# Controller.net
KiCad netlist of a schematic drawn in Altium Designer
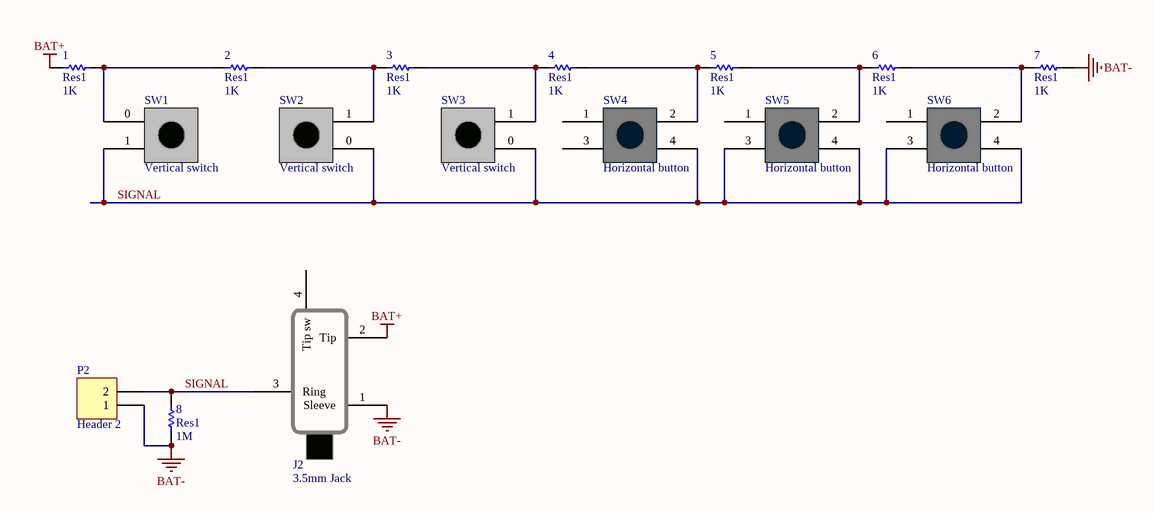
[diagram p0: Controller.SchDoc]

(export (version "E")
  (design (tool "Eeschema 10.0.6"))
  (components
    (comp (ref "1")
      (value "Res1")
      (footprint "6-0805_N")
      (description "Resistor")
      (fields (field (name "ALTIUM_VALUE") "1K") (field (name "PUBLISHER") "Altium Limited"))
      (libsource (lib "Miscellaneous Devices") (part "Res1"))
    )
    (comp (ref "2")
      (value "Res1")
      (footprint "6-0805_N")
      (description "Resistor")
      (fields (field (name "ALTIUM_VALUE") "1K") (field (name "PUBLISHER") "Altium Limited"))
      (libsource (lib "Miscellaneous Devices") (part "Res1"))
    )
    (comp (ref "3")
      (value "Res1")
      (footprint "6-0805_N")
      (description "Resistor")
      (fields (field (name "ALTIUM_VALUE") "1K") (field (name "PUBLISHER") "Altium Limited"))
      (libsource (lib "Miscellaneous Devices") (part "Res1"))
    )
    (comp (ref "4")
      (value "Res1")
      (footprint "6-0805_N")
      (description "Resistor")
      (fields (field (name "ALTIUM_VALUE") "1K") (field (name "PUBLISHER") "Altium Limited"))
      (libsource (lib "Miscellaneous Devices") (part "Res1"))
    )
    (comp (ref "5")
      (value "Res1")
      (footprint "6-0805_N")
      (description "Resistor")
      (fields (field (name "ALTIUM_VALUE") "1K") (field (name "PUBLISHER") "Altium Limited"))
      (libsource (lib "Miscellaneous Devices") (part "Res1"))
    )
    (comp (ref "6")
      (value "Res1")
      (footprint "6-0805_N")
      (description "Resistor")
      (fields (field (name "ALTIUM_VALUE") "1K") (field (name "PUBLISHER") "Altium Limited"))
      (libsource (lib "Miscellaneous Devices") (part "Res1"))
    )
    (comp (ref "7")
      (value "Res1")
      (footprint "6-0805_N")
      (description "Resistor")
      (fields (field (name "ALTIUM_VALUE") "1K") (field (name "PUBLISHER") "Altium Limited"))
      (libsource (lib "Miscellaneous Devices") (part "Res1"))
    )
    (comp (ref "8")
      (value "Res1")
      (footprint "6-0805_M")
      (description "Resistor")
      (fields (field (name "ALTIUM_VALUE") "1M") (field (name "PUBLISHER") "Altium Limited"))
      (libsource (lib "Miscellaneous Devices") (part "Res1"))
    )
    (comp (ref "J2")
      (value "3.5mm Jack")
      (footprint "Phonejack")
      (libsource (lib "Phonejack") (part "Phonejack"))
    )
    (comp (ref "P2")
      (value "Header 2")
      (footprint "HDR1X2")
      (description "Header, 2-Pin")
      (fields (field (name "PUBLISHER") "Altium Limited"))
      (libsource (lib "Miscellaneous Connectors") (part "Header 2"))
    )
    (comp (ref "SW1") (value "Vertical switch") (footprint "Btn_Vert") (libsource (lib "") (part "SWVERT_1")))
    (comp (ref "SW2")
      (value "Vertical switch")
      (footprint "Btn_Vert")
      (libsource (lib "Btn_Vert") (part "SWVERT"))
    )
    (comp (ref "SW3")
      (value "Vertical switch")
      (footprint "Btn_Vert")
      (libsource (lib "Btn_Vert") (part "SWVERT"))
    )
    (comp (ref "SW4")
      (value "Horizontal button")
      (footprint "Btn_Horiz")
      (libsource (lib "Btn_Horiz") (part "HORIZBTN"))
    )
    (comp (ref "SW5")
      (value "Horizontal button")
      (footprint "Btn_Horiz")
      (libsource (lib "Btn_Horiz") (part "HORIZBTN"))
    )
    (comp (ref "SW6")
      (value "Horizontal button")
      (footprint "Btn_Horiz")
      (libsource (lib "Btn_Horiz") (part "HORIZBTN"))
    )
  )
  (nets
    (net (code "1") (name "/SIGNAL") (class "Default")
      (node (ref "8") (pin "1") (pinfunction "1_1") (pintype "passive"))
      (node (ref "J2") (pin "3") (pinfunction "Ring_3") (pintype "passive"))
      (node (ref "P2") (pin "2") (pinfunction "2_2") (pintype "passive"))
      (node (ref "SW1") (pin "1") (pintype "passive"))
      (node (ref "SW2") (pin "0") (pintype "passive"))
      (node (ref "SW3") (pin "0") (pintype "passive"))
      (node (ref "SW4") (pin "4") (pintype "passive"))
      (node (ref "SW5") (pin "3") (pintype "passive"))
      (node (ref "SW5") (pin "4") (pintype "passive"))
      (node (ref "SW6") (pin "3") (pintype "passive"))
      (node (ref "SW6") (pin "4") (pintype "passive"))
    )
    (net (code "2") (name "BAT+") (class "Default")
      (node (ref "1") (pin "2") (pinfunction "2_2") (pintype "passive"))
      (node (ref "J2") (pin "2") (pinfunction "Tip_2") (pintype "passive"))
    )
    (net (code "3") (name "BAT-") (class "Default")
      (node (ref "7") (pin "1") (pinfunction "1_1") (pintype "passive"))
      (node (ref "8") (pin "2") (pinfunction "2_2") (pintype "passive"))
      (node (ref "J2") (pin "1") (pinfunction "Sleeve_1") (pintype "passive"))
      (node (ref "P2") (pin "1") (pinfunction "1_1") (pintype "passive"))
    )
    (net (code "4") (name "Net-(1-Pad1)") (class "Default")
      (node (ref "1") (pin "1") (pinfunction "1_1") (pintype "passive"))
      (node (ref "2") (pin "2") (pinfunction "2_2") (pintype "passive"))
      (node (ref "SW1") (pin "0") (pintype "passive"))
    )
    (net (code "5") (name "Net-(2-Pad1)") (class "Default")
      (node (ref "2") (pin "1") (pinfunction "1_1") (pintype "passive"))
      (node (ref "3") (pin "2") (pinfunction "2_2") (pintype "passive"))
      (node (ref "SW2") (pin "1") (pintype "passive"))
    )
    (net (code "6") (name "Net-(3-Pad1)") (class "Default")
      (node (ref "3") (pin "1") (pinfunction "1_1") (pintype "passive"))
      (node (ref "4") (pin "2") (pinfunction "2_2") (pintype "passive"))
      (node (ref "SW3") (pin "1") (pintype "passive"))
    )
    (net (code "7") (name "Net-(4-Pad1)") (class "Default")
      (node (ref "4") (pin "1") (pinfunction "1_1") (pintype "passive"))
      (node (ref "5") (pin "2") (pinfunction "2_2") (pintype "passive"))
      (node (ref "SW4") (pin "2") (pintype "passive"))
    )
    (net (code "8") (name "Net-(5-Pad1)") (class "Default")
      (node (ref "5") (pin "1") (pinfunction "1_1") (pintype "passive"))
      (node (ref "6") (pin "1") (pinfunction "1_1") (pintype "passive"))
      (node (ref "SW5") (pin "2") (pintype "passive"))
    )
    (net (code "9") (name "Net-(6-Pad2)") (class "Default")
      (node (ref "6") (pin "2") (pinfunction "2_2") (pintype "passive"))
      (node (ref "7") (pin "2") (pinfunction "2_2") (pintype "passive"))
      (node (ref "SW6") (pin "2") (pintype "passive"))
    )
    (net (code "10") (name "unconnected-(J2-Tip_sw-Pad4)") (class "Default")
      (node (ref "J2") (pin "4") (pinfunction "Tip_sw_4") (pintype "passive"))
    )
    (net (code "11") (name "unconnected-(SW4-Pad1)") (class "Default")
      (node (ref "SW4") (pin "1") (pintype "passive"))
    )
    (net (code "12") (name "unconnected-(SW4-Pad3)") (class "Default")
      (node (ref "SW4") (pin "3") (pintype "passive"))
    )
    (net (code "13") (name "unconnected-(SW5-Pad1)") (class "Default")
      (node (ref "SW5") (pin "1") (pintype "passive"))
    )
    (net (code "14") (name "unconnected-(SW6-Pad1)") (class "Default")
      (node (ref "SW6") (pin "1") (pintype "passive"))
    )
  )
)
